# ESIMA_E-Meter_Radio.net
KiCad netlist of a schematic drawn in Altium Designer
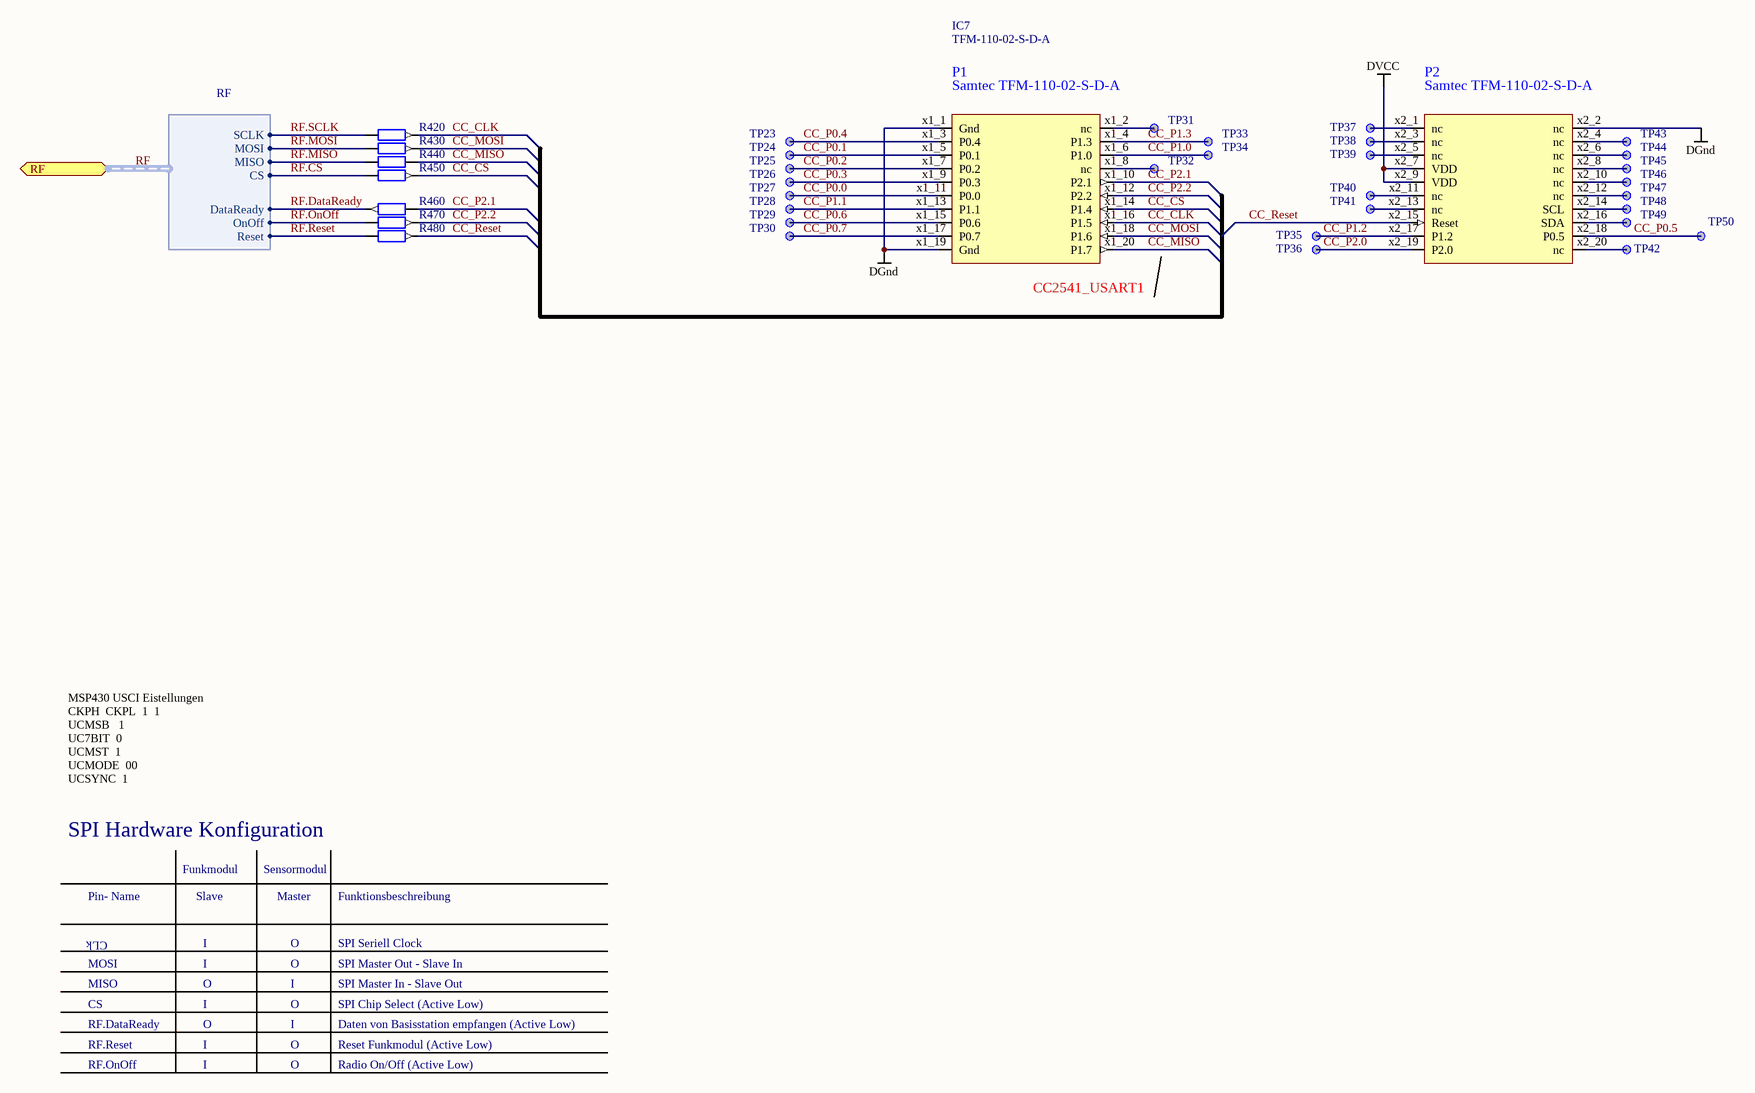
[diagram p0: ESIMA E-Meter_Radio.SchDoc]

(export (version "E")
  (design (tool "Eeschema 10.0.6"))
  (components
    (comp (ref "IC7")
      (value "TFM-110-02-S-D-A")
      (footprint "CC2530EM-Board")
      (description "Samtec Connecotor")
      (libsource (lib "JM_Halbleiter") (part "CC2530EM"))
    )
    (comp (ref "R42")
      (value "0")
      (footprint "RESC1608N")
      (description "RESC1608 (R0603)")
      (libsource (lib "JM_Widerstaende") (part "RESC1608 (R0603)"))
    )
    (comp (ref "R43")
      (value "0")
      (footprint "RESC1608N")
      (description "RESC1608 (R0603)")
      (libsource (lib "JM_Widerstaende") (part "RESC1608 (R0603)"))
    )
    (comp (ref "R44")
      (value "0")
      (footprint "RESC1608N")
      (description "RESC1608 (R0603)")
      (libsource (lib "JM_Widerstaende") (part "RESC1608 (R0603)"))
    )
    (comp (ref "R45")
      (value "0")
      (footprint "RESC1608N")
      (description "RESC1608 (R0603)")
      (libsource (lib "JM_Widerstaende") (part "RESC1608 (R0603)"))
    )
    (comp (ref "R46")
      (value "0")
      (footprint "RESC1608N")
      (description "RESC1608 (R0603)")
      (libsource (lib "JM_Widerstaende") (part "RESC1608 (R0603)"))
    )
    (comp (ref "R47")
      (value "0")
      (footprint "RESC1608N")
      (description "RESC1608 (R0603)")
      (libsource (lib "JM_Widerstaende") (part "RESC1608 (R0603)"))
    )
    (comp (ref "R48")
      (value "0")
      (footprint "RESC1608N")
      (description "RESC1608 (R0603)")
      (libsource (lib "JM_Widerstaende") (part "RESC1608 (R0603)"))
    )
    (comp (ref "TP23")
      (value "Testpoint 1mm")
      (footprint "Testpoint 1mm")
      (libsource (lib "HSG-IMIT_JuergenMerz") (part "Tespoint 1mm"))
    )
    (comp (ref "TP24")
      (value "Testpoint 1mm")
      (footprint "Testpoint 1mm")
      (libsource (lib "HSG-IMIT_JuergenMerz") (part "Tespoint 1mm"))
    )
    (comp (ref "TP25")
      (value "Testpoint 1mm")
      (footprint "Testpoint 1mm")
      (libsource (lib "HSG-IMIT_JuergenMerz") (part "Tespoint 1mm"))
    )
    (comp (ref "TP26")
      (value "Testpoint 1mm")
      (footprint "Testpoint 1mm")
      (libsource (lib "HSG-IMIT_JuergenMerz") (part "Tespoint 1mm"))
    )
    (comp (ref "TP27")
      (value "Testpoint 1mm")
      (footprint "Testpoint 1mm")
      (libsource (lib "HSG-IMIT_JuergenMerz") (part "Tespoint 1mm"))
    )
    (comp (ref "TP28")
      (value "Testpoint 1mm")
      (footprint "Testpoint 1mm")
      (libsource (lib "HSG-IMIT_JuergenMerz") (part "Tespoint 1mm"))
    )
    (comp (ref "TP29")
      (value "Testpoint 1mm")
      (footprint "Testpoint 1mm")
      (libsource (lib "HSG-IMIT_JuergenMerz") (part "Tespoint 1mm"))
    )
    (comp (ref "TP30")
      (value "Testpoint 1mm")
      (footprint "Testpoint 1mm")
      (libsource (lib "HSG-IMIT_JuergenMerz") (part "Tespoint 1mm"))
    )
    (comp (ref "TP31")
      (value "Testpoint 1mm")
      (footprint "Testpoint 1mm")
      (libsource (lib "HSG-IMIT_JuergenMerz") (part "Tespoint 1mm"))
    )
    (comp (ref "TP32")
      (value "Testpoint 1mm")
      (footprint "Testpoint 1mm")
      (libsource (lib "HSG-IMIT_JuergenMerz") (part "Tespoint 1mm"))
    )
    (comp (ref "TP33")
      (value "Testpoint 1mm")
      (footprint "Testpoint 1mm")
      (libsource (lib "HSG-IMIT_JuergenMerz") (part "Tespoint 1mm"))
    )
    (comp (ref "TP34")
      (value "Testpoint 1mm")
      (footprint "Testpoint 1mm")
      (libsource (lib "HSG-IMIT_JuergenMerz") (part "Tespoint 1mm"))
    )
    (comp (ref "TP35")
      (value "Testpoint 1mm")
      (footprint "Testpoint 1mm")
      (libsource (lib "HSG-IMIT_JuergenMerz") (part "Tespoint 1mm"))
    )
    (comp (ref "TP36")
      (value "Testpoint 1mm")
      (footprint "Testpoint 1mm")
      (libsource (lib "HSG-IMIT_JuergenMerz") (part "Tespoint 1mm"))
    )
    (comp (ref "TP37")
      (value "Testpoint 1mm")
      (footprint "Testpoint 1mm")
      (libsource (lib "HSG-IMIT_JuergenMerz") (part "Tespoint 1mm"))
    )
    (comp (ref "TP38")
      (value "Testpoint 1mm")
      (footprint "Testpoint 1mm")
      (libsource (lib "HSG-IMIT_JuergenMerz") (part "Tespoint 1mm"))
    )
    (comp (ref "TP39")
      (value "Testpoint 1mm")
      (footprint "Testpoint 1mm")
      (libsource (lib "HSG-IMIT_JuergenMerz") (part "Tespoint 1mm"))
    )
    (comp (ref "TP40")
      (value "Testpoint 1mm")
      (footprint "Testpoint 1mm")
      (libsource (lib "HSG-IMIT_JuergenMerz") (part "Tespoint 1mm"))
    )
    (comp (ref "TP41")
      (value "Testpoint 1mm")
      (footprint "Testpoint 1mm")
      (libsource (lib "HSG-IMIT_JuergenMerz") (part "Tespoint 1mm"))
    )
    (comp (ref "TP42")
      (value "Testpoint 1mm")
      (footprint "Testpoint 1mm")
      (libsource (lib "HSG-IMIT_JuergenMerz") (part "Tespoint 1mm"))
    )
    (comp (ref "TP43")
      (value "Testpoint 1mm")
      (footprint "Testpoint 1mm")
      (libsource (lib "HSG-IMIT_JuergenMerz") (part "Tespoint 1mm"))
    )
    (comp (ref "TP44")
      (value "Testpoint 1mm")
      (footprint "Testpoint 1mm")
      (libsource (lib "HSG-IMIT_JuergenMerz") (part "Tespoint 1mm"))
    )
    (comp (ref "TP45")
      (value "Testpoint 1mm")
      (footprint "Testpoint 1mm")
      (libsource (lib "HSG-IMIT_JuergenMerz") (part "Tespoint 1mm"))
    )
    (comp (ref "TP46")
      (value "Testpoint 1mm")
      (footprint "Testpoint 1mm")
      (libsource (lib "HSG-IMIT_JuergenMerz") (part "Tespoint 1mm"))
    )
    (comp (ref "TP47")
      (value "Testpoint 1mm")
      (footprint "Testpoint 1mm")
      (libsource (lib "HSG-IMIT_JuergenMerz") (part "Tespoint 1mm"))
    )
    (comp (ref "TP48")
      (value "Testpoint 1mm")
      (footprint "Testpoint 1mm")
      (libsource (lib "HSG-IMIT_JuergenMerz") (part "Tespoint 1mm"))
    )
    (comp (ref "TP49")
      (value "Testpoint 1mm")
      (footprint "Testpoint 1mm")
      (libsource (lib "HSG-IMIT_JuergenMerz") (part "Tespoint 1mm"))
    )
    (comp (ref "TP50")
      (value "Testpoint 1mm")
      (footprint "Testpoint 1mm")
      (libsource (lib "HSG-IMIT_JuergenMerz") (part "Tespoint 1mm"))
    )
  )
  (nets
    (net (code "2") (name "/CC_CLK") (class "Default")
      (node (ref "IC7") (pin "x1_16") (pinfunction "P1.5_x1_16") (pintype "input"))
      (node (ref "R42") (pin "1") (pinfunction "1_1") (pintype "output"))
    )
    (net (code "3") (name "/CC_CS") (class "Default")
      (node (ref "IC7") (pin "x1_14") (pinfunction "P1.4_x1_14") (pintype "input"))
      (node (ref "R45") (pin "1") (pinfunction "1_1") (pintype "output"))
    )
    (net (code "4") (name "/CC_MISO") (class "Default")
      (node (ref "IC7") (pin "x1_20") (pinfunction "P1.7_x1_20") (pintype "output"))
      (node (ref "R44") (pin "1") (pinfunction "1_1") (pintype "output"))
    )
    (net (code "5") (name "/CC_MOSI") (class "Default")
      (node (ref "IC7") (pin "x1_18") (pinfunction "P1.6_x1_18") (pintype "input"))
      (node (ref "R43") (pin "1") (pinfunction "1_1") (pintype "output"))
    )
    (net (code "6") (name "/CC_P0.0") (class "Default")
      (node (ref "IC7") (pin "x1_11") (pinfunction "P0.0_x1_11") (pintype "bidirectional"))
      (node (ref "TP27") (pin "1") (pintype "passive"))
    )
    (net (code "7") (name "/CC_P0.1") (class "Default")
      (node (ref "IC7") (pin "x1_5") (pinfunction "P0.1_x1_5") (pintype "bidirectional"))
      (node (ref "TP24") (pin "1") (pintype "passive"))
    )
    (net (code "8") (name "/CC_P0.2") (class "Default")
      (node (ref "IC7") (pin "x1_7") (pinfunction "P0.2_x1_7") (pintype "bidirectional"))
      (node (ref "TP25") (pin "1") (pintype "passive"))
    )
    (net (code "9") (name "/CC_P0.3") (class "Default")
      (node (ref "IC7") (pin "x1_9") (pinfunction "P0.3_x1_9") (pintype "bidirectional"))
      (node (ref "TP26") (pin "1") (pintype "passive"))
    )
    (net (code "10") (name "/CC_P0.4") (class "Default")
      (node (ref "IC7") (pin "x1_3") (pinfunction "P0.4_x1_3") (pintype "bidirectional"))
      (node (ref "TP23") (pin "1") (pintype "passive"))
    )
    (net (code "11") (name "/CC_P0.5") (class "Default")
      (node (ref "IC7") (pin "x2_18") (pinfunction "P0.5_x2_18") (pintype "bidirectional"))
      (node (ref "TP50") (pin "1") (pintype "passive"))
    )
    (net (code "12") (name "/CC_P0.6") (class "Default")
      (node (ref "IC7") (pin "x1_15") (pinfunction "P0.6_x1_15") (pintype "bidirectional"))
      (node (ref "TP29") (pin "1") (pintype "passive"))
    )
    (net (code "13") (name "/CC_P0.7") (class "Default")
      (node (ref "IC7") (pin "x1_17") (pinfunction "P0.7_x1_17") (pintype "bidirectional"))
      (node (ref "TP30") (pin "1") (pintype "passive"))
    )
    (net (code "14") (name "/CC_P1.0") (class "Default")
      (node (ref "IC7") (pin "x1_6") (pinfunction "P1.0_x1_6") (pintype "bidirectional"))
      (node (ref "TP34") (pin "1") (pintype "passive"))
    )
    (net (code "15") (name "/CC_P1.1") (class "Default")
      (node (ref "IC7") (pin "x1_13") (pinfunction "P1.1_x1_13") (pintype "bidirectional"))
      (node (ref "TP28") (pin "1") (pintype "passive"))
    )
    (net (code "16") (name "/CC_P1.2") (class "Default")
      (node (ref "IC7") (pin "x2_17") (pinfunction "P1.2_x2_17") (pintype "bidirectional"))
      (node (ref "TP35") (pin "1") (pintype "passive"))
    )
    (net (code "17") (name "/CC_P1.3") (class "Default")
      (node (ref "IC7") (pin "x1_4") (pinfunction "P1.3_x1_4") (pintype "bidirectional"))
      (node (ref "TP33") (pin "1") (pintype "passive"))
    )
    (net (code "18") (name "/CC_P2.0") (class "Default")
      (node (ref "IC7") (pin "x2_19") (pinfunction "P2.0_x2_19") (pintype "bidirectional"))
      (node (ref "TP36") (pin "1") (pintype "passive"))
    )
    (net (code "19") (name "/CC_P2.1") (class "Default")
      (node (ref "IC7") (pin "x1_10") (pinfunction "P2.1_x1_10") (pintype "output"))
      (node (ref "R46") (pin "1") (pinfunction "1_1") (pintype "output"))
    )
    (net (code "20") (name "/CC_P2.2") (class "Default")
      (node (ref "IC7") (pin "x1_12") (pinfunction "P2.2_x1_12") (pintype "input"))
      (node (ref "R47") (pin "1") (pinfunction "1_1") (pintype "output"))
    )
    (net (code "21") (name "/CC_Reset") (class "Default")
      (node (ref "IC7") (pin "x2_15") (pinfunction "Reset_x2_15") (pintype "input"))
      (node (ref "R48") (pin "1") (pinfunction "1_1") (pintype "output"))
    )
    (net (code "22") (name "/RF.CS") (class "Default")
      (node (ref "R45") (pin "2") (pinfunction "2_2") (pintype "passive"))
    )
    (net (code "23") (name "/RF.DataReady") (class "Default")
      (node (ref "R46") (pin "2") (pinfunction "2_2") (pintype "passive"))
    )
    (net (code "24") (name "/RF.MISO") (class "Default")
      (node (ref "R44") (pin "2") (pinfunction "2_2") (pintype "passive"))
    )
    (net (code "25") (name "/RF.MOSI") (class "Default")
      (node (ref "R43") (pin "2") (pinfunction "2_2") (pintype "passive"))
    )
    (net (code "26") (name "/RF.OnOff") (class "Default")
      (node (ref "R47") (pin "2") (pinfunction "2_2") (pintype "passive"))
    )
    (net (code "27") (name "/RF.Reset") (class "Default")
      (node (ref "R48") (pin "2") (pinfunction "2_2") (pintype "passive"))
    )
    (net (code "28") (name "/RF.SCLK") (class "Default")
      (node (ref "R42") (pin "2") (pinfunction "2_2") (pintype "passive"))
    )
    (net (code "30") (name "DGnd") (class "Default")
      (node (ref "IC7") (pin "x1_1") (pinfunction "Gnd_x1_1") (pintype "power_in"))
      (node (ref "IC7") (pin "x1_19") (pinfunction "Gnd_x1_19") (pintype "power_in"))
      (node (ref "IC7") (pin "x2_2") (pinfunction "nc_x2_2") (pintype "passive"))
    )
    (net (code "31") (name "DVCC") (class "Default")
      (node (ref "IC7") (pin "x2_7") (pinfunction "VDD_x2_7") (pintype "power_in"))
      (node (ref "IC7") (pin "x2_9") (pinfunction "VDD_x2_9") (pintype "power_in"))
    )
    (net (code "32") (name "Net-(IC7-SCL)") (class "Default")
      (node (ref "IC7") (pin "x2_14") (pinfunction "SCL_x2_14") (pintype "open_collector"))
      (node (ref "TP48") (pin "1") (pintype "passive"))
    )
    (net (code "33") (name "Net-(IC7-SDA)") (class "Default")
      (node (ref "IC7") (pin "x2_16") (pinfunction "SDA_x2_16") (pintype "open_collector"))
      (node (ref "TP49") (pin "1") (pintype "passive"))
    )
    (net (code "34") (name "Net-(IC7-nc-Padx1_2)") (class "Default")
      (node (ref "IC7") (pin "x1_2") (pinfunction "nc_x1_2") (pintype "passive"))
      (node (ref "TP31") (pin "1") (pintype "passive"))
    )
    (net (code "35") (name "Net-(IC7-nc-Padx1_8)") (class "Default")
      (node (ref "IC7") (pin "x1_8") (pinfunction "nc_x1_8") (pintype "passive"))
      (node (ref "TP32") (pin "1") (pintype "passive"))
    )
    (net (code "36") (name "Net-(IC7-nc-Padx2_1)") (class "Default")
      (node (ref "IC7") (pin "x2_1") (pinfunction "nc_x2_1") (pintype "passive"))
      (node (ref "TP37") (pin "1") (pintype "passive"))
    )
    (net (code "37") (name "Net-(IC7-nc-Padx2_3)") (class "Default")
      (node (ref "IC7") (pin "x2_3") (pinfunction "nc_x2_3") (pintype "passive"))
      (node (ref "TP38") (pin "1") (pintype "passive"))
    )
    (net (code "38") (name "Net-(IC7-nc-Padx2_4)") (class "Default")
      (node (ref "IC7") (pin "x2_4") (pinfunction "nc_x2_4") (pintype "passive"))
      (node (ref "TP43") (pin "1") (pintype "passive"))
    )
    (net (code "39") (name "Net-(IC7-nc-Padx2_5)") (class "Default")
      (node (ref "IC7") (pin "x2_5") (pinfunction "nc_x2_5") (pintype "passive"))
      (node (ref "TP39") (pin "1") (pintype "passive"))
    )
    (net (code "40") (name "Net-(IC7-nc-Padx2_6)") (class "Default")
      (node (ref "IC7") (pin "x2_6") (pinfunction "nc_x2_6") (pintype "passive"))
      (node (ref "TP44") (pin "1") (pintype "passive"))
    )
    (net (code "41") (name "Net-(IC7-nc-Padx2_8)") (class "Default")
      (node (ref "IC7") (pin "x2_8") (pinfunction "nc_x2_8") (pintype "passive"))
      (node (ref "TP45") (pin "1") (pintype "passive"))
    )
    (net (code "42") (name "Net-(IC7-nc-Padx2_10)") (class "Default")
      (node (ref "IC7") (pin "x2_10") (pinfunction "nc_x2_10") (pintype "passive"))
      (node (ref "TP46") (pin "1") (pintype "passive"))
    )
    (net (code "43") (name "Net-(IC7-nc-Padx2_11)") (class "Default")
      (node (ref "IC7") (pin "x2_11") (pinfunction "nc_x2_11") (pintype "passive"))
      (node (ref "TP40") (pin "1") (pintype "passive"))
    )
    (net (code "44") (name "Net-(IC7-nc-Padx2_12)") (class "Default")
      (node (ref "IC7") (pin "x2_12") (pinfunction "nc_x2_12") (pintype "passive"))
      (node (ref "TP47") (pin "1") (pintype "passive"))
    )
    (net (code "45") (name "Net-(IC7-nc-Padx2_13)") (class "Default")
      (node (ref "IC7") (pin "x2_13") (pinfunction "nc_x2_13") (pintype "passive"))
      (node (ref "TP41") (pin "1") (pintype "passive"))
    )
    (net (code "46") (name "Net-(IC7-nc-Padx2_20)") (class "Default")
      (node (ref "IC7") (pin "x2_20") (pinfunction "nc_x2_20") (pintype "passive"))
      (node (ref "TP42") (pin "1") (pintype "passive"))
    )
  )
)
